# remora-2-sensors.net
KiCad netlist of a schematic drawn in Altium Designer
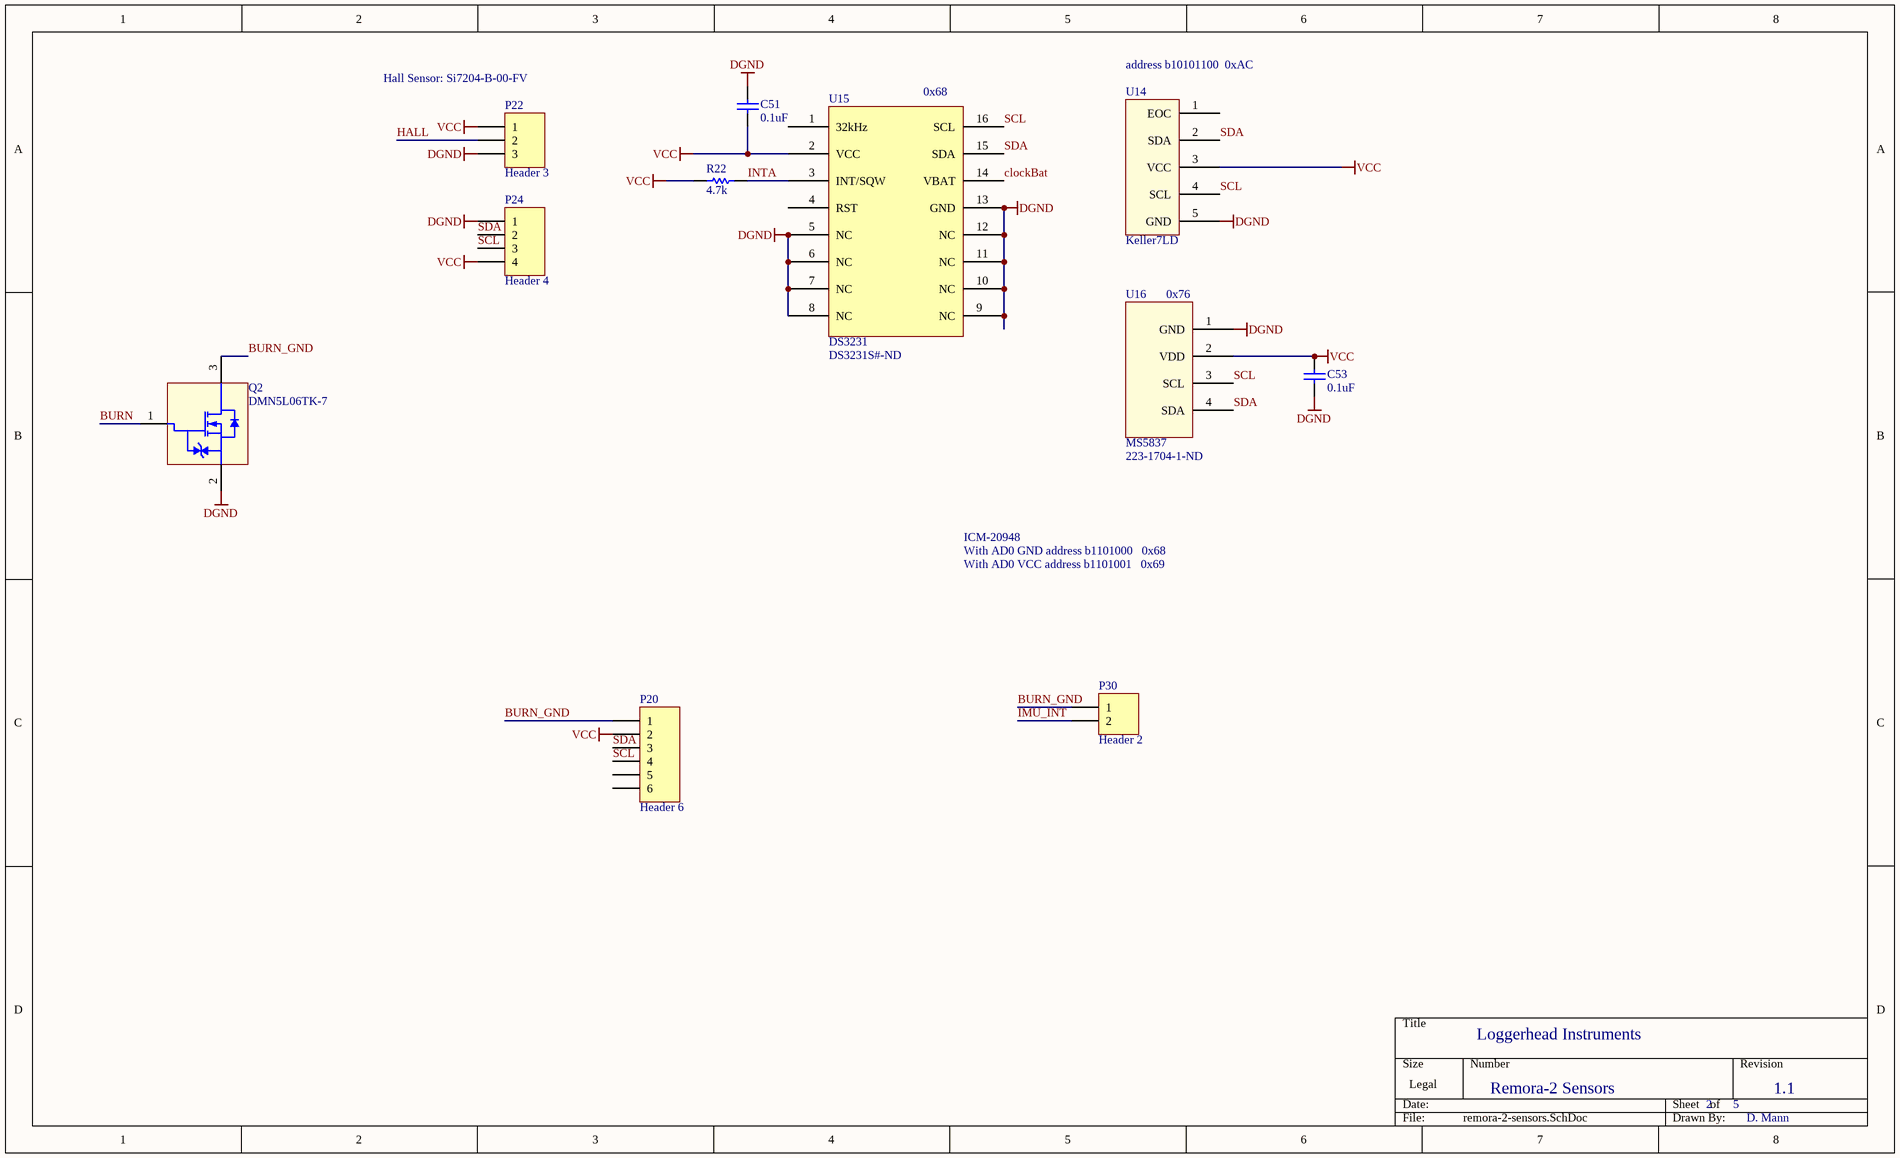
[diagram p0: remora-2-sensors.SchDoc]

(export (version "E")
  (design (tool "Eeschema 10.0.6"))
  (components
    (comp (ref "C51")
      (value "0.1uF")
      (footprint "0402")
      (description "Ceramic Chip Capacitor - Standard")
      (fields (field (name "PUBLISHER") "Altium Limited"))
      (libsource (lib "KEMET Chip Capacitor") (part "C0402"))
    )
    (comp (ref "C53")
      (value "0.1uF")
      (footprint "0402")
      (description "Ceramic Chip Capacitor - Standard")
      (fields (field (name "PUBLISHER") "Altium Limited"))
      (libsource (lib "KEMET Chip Capacitor") (part "C0402"))
    )
    (comp (ref "P20")
      (value "Header 6")
      (footprint "HDR1X6")
      (description "Header, 6-Pin")
      (fields (field (name "PUBLISHER") "Altium Limited"))
      (libsource (lib "Miscellaneous Connectors") (part "Header 6"))
    )
    (comp (ref "P22")
      (value "Header 3")
      (footprint "HDR1X3")
      (description "Header, 3-Pin")
      (fields (field (name "PUBLISHER") "Altium Limited"))
      (libsource (lib "Miscellaneous Connectors") (part "Header 3"))
    )
    (comp (ref "P24")
      (value "Header 4")
      (footprint "HDR1X4")
      (description "Header, 4-Pin")
      (fields (field (name "PUBLISHER") "Altium Limited"))
      (libsource (lib "Miscellaneous Connectors") (part "Header 4"))
    )
    (comp (ref "P30")
      (value "Header 2")
      (footprint "HDR1X2")
      (description "Header, 2-Pin")
      (fields (field (name "PUBLISHER") "Altium Limited"))
      (libsource (lib "Miscellaneous Connectors") (part "Header 2"))
    )
    (comp (ref "Q2")
      (value "DMN5L06TK-7")
      (footprint "SOT-523")
      (description "Ultra-low leakage Enhanced MOSFET")
      (fields
        (field (name "CREATOR AND DATE") "Will Flanery 2010-09-02")
        (field (name "FOOTPRINT VERIFIED BY") "*")
        (field (name "SCHEMATIC VERIFIED BY") "*")
        (field (name "VENDOR INFO VERIFIED BY") "*")
      )
      (libsource (lib "Flanery") (part "FET DMN5L06TK-7"))
    )
    (comp (ref "R22")
      (value "4.7k")
      (footprint "3-0603")
      (fields (field (name "PUBLISHER") "Altium Limited"))
      (libsource (lib "Panasonic Resistor") (part "ERJ3RK"))
    )
    (comp (ref "U14")
      (value "Keller7LD")
      (footprint "Keller7LD")
      (description "Keller Pressure/Temp")
      (libsource (lib "Loggerhead") (part "Keller 7LD"))
    )
    (comp (ref "U15")
      (value "DS3231")
      (footprint "DS3231")
      (fields (field (name "SUPPLIER PART NUMBER 1") "DS3231S#-ND"))
      (libsource (lib "Loggerhead") (part "DS3231"))
    )
    (comp (ref "U16")
      (value "MS5837")
      (footprint "MS5837")
      (description "Pressure/Temp")
      (fields (field (name "SUPPLIER PART NUMBER 1") "223-1704-1-ND"))
      (libsource (lib "Loggerhead") (part "MS5837"))
    )
  )
  (nets
    (net (code "1") (name "/BURN") (class "Default")
      (node (ref "Q2") (pin "1") (pinfunction "G_1") (pintype "passive"))
    )
    (net (code "2") (name "/BURN_GND") (class "Default")
      (node (ref "P20") (pin "1") (pinfunction "1_1") (pintype "passive"))
      (node (ref "P30") (pin "1") (pinfunction "1_1") (pintype "passive"))
      (node (ref "Q2") (pin "3") (pinfunction "D_3") (pintype "passive"))
    )
    (net (code "3") (name "/HALL") (class "Default")
      (node (ref "P22") (pin "2") (pinfunction "2_2") (pintype "passive"))
    )
    (net (code "4") (name "/IMU_INT") (class "Default")
      (node (ref "P30") (pin "2") (pinfunction "2_2") (pintype "passive"))
    )
    (net (code "5") (name "/INTA") (class "Default")
      (node (ref "R22") (pin "2") (pinfunction "2_2") (pintype "passive"))
      (node (ref "U15") (pin "3") (pinfunction "INT/SQW_3") (pintype "passive"))
    )
    (net (code "6") (name "/SCL") (class "Default")
      (node (ref "P20") (pin "4") (pinfunction "4_4") (pintype "passive"))
      (node (ref "P24") (pin "3") (pinfunction "3_3") (pintype "passive"))
      (node (ref "U14") (pin "4") (pinfunction "SCL_4") (pintype "passive"))
      (node (ref "U15") (pin "16") (pinfunction "SCL_16") (pintype "passive"))
      (node (ref "U16") (pin "3") (pinfunction "SCL_3") (pintype "passive"))
    )
    (net (code "7") (name "/SDA") (class "Default")
      (node (ref "P20") (pin "3") (pinfunction "3_3") (pintype "passive"))
      (node (ref "P24") (pin "2") (pinfunction "2_2") (pintype "passive"))
      (node (ref "U14") (pin "2") (pinfunction "SDA_2") (pintype "passive"))
      (node (ref "U15") (pin "15") (pinfunction "SDA_15") (pintype "passive"))
      (node (ref "U16") (pin "4") (pinfunction "SDA_4") (pintype "passive"))
    )
    (net (code "8") (name "/clockBat") (class "Default")
      (node (ref "U15") (pin "14") (pinfunction "VBAT_14") (pintype "power_in"))
    )
    (net (code "9") (name "DGND") (class "Default")
      (node (ref "C51") (pin "1") (pinfunction "1_1") (pintype "passive"))
      (node (ref "C53") (pin "1") (pinfunction "1_1") (pintype "passive"))
      (node (ref "P22") (pin "3") (pinfunction "3_3") (pintype "passive"))
      (node (ref "P24") (pin "1") (pinfunction "1_1") (pintype "passive"))
      (node (ref "Q2") (pin "2") (pinfunction "S_2") (pintype "passive"))
      (node (ref "U14") (pin "5") (pinfunction "GND_5") (pintype "passive"))
      (node (ref "U15") (pin "10") (pinfunction "NC_10") (pintype "passive"))
      (node (ref "U15") (pin "11") (pinfunction "NC_11") (pintype "passive"))
      (node (ref "U15") (pin "12") (pinfunction "NC_12") (pintype "passive"))
      (node (ref "U15") (pin "13") (pinfunction "GND_13") (pintype "passive"))
      (node (ref "U15") (pin "5") (pinfunction "NC_5") (pintype "passive"))
      (node (ref "U15") (pin "6") (pinfunction "NC_6") (pintype "passive"))
      (node (ref "U15") (pin "7") (pinfunction "NC_7") (pintype "passive"))
      (node (ref "U15") (pin "8") (pinfunction "NC_8") (pintype "passive"))
      (node (ref "U15") (pin "9") (pinfunction "NC_9") (pintype "passive"))
      (node (ref "U16") (pin "1") (pinfunction "GND_1") (pintype "passive"))
    )
    (net (code "10") (name "VCC") (class "Default")
      (node (ref "C51") (pin "2") (pinfunction "2_2") (pintype "passive"))
      (node (ref "C53") (pin "2") (pinfunction "2_2") (pintype "passive"))
      (node (ref "P20") (pin "2") (pinfunction "2_2") (pintype "passive"))
      (node (ref "P22") (pin "1") (pinfunction "1_1") (pintype "passive"))
      (node (ref "P24") (pin "4") (pinfunction "4_4") (pintype "passive"))
      (node (ref "R22") (pin "1") (pinfunction "1_1") (pintype "passive"))
      (node (ref "U14") (pin "3") (pinfunction "VCC_3") (pintype "passive"))
      (node (ref "U15") (pin "2") (pinfunction "VCC_2") (pintype "power_in"))
      (node (ref "U16") (pin "2") (pinfunction "VDD_2") (pintype "passive"))
    )
    (net (code "11") (name "unconnected-(P20-Pad5)") (class "Default")
      (node (ref "P20") (pin "5") (pinfunction "5_5") (pintype "passive"))
    )
    (net (code "12") (name "unconnected-(P20-Pad6)") (class "Default")
      (node (ref "P20") (pin "6") (pinfunction "6_6") (pintype "passive"))
    )
    (net (code "13") (name "unconnected-(U14-EOC-Pad1)") (class "Default")
      (node (ref "U14") (pin "1") (pinfunction "EOC_1") (pintype "passive"))
    )
    (net (code "14") (name "unconnected-(U15-32kHz-Pad1)") (class "Default")
      (node (ref "U15") (pin "1") (pinfunction "32kHz_1") (pintype "passive"))
    )
    (net (code "15") (name "unconnected-(U15-RST-Pad4)") (class "Default")
      (node (ref "U15") (pin "4") (pinfunction "RST_4") (pintype "passive"))
    )
  )
)
